# fpga_io.net
KiCad netlist of a schematic drawn in Altium Designer
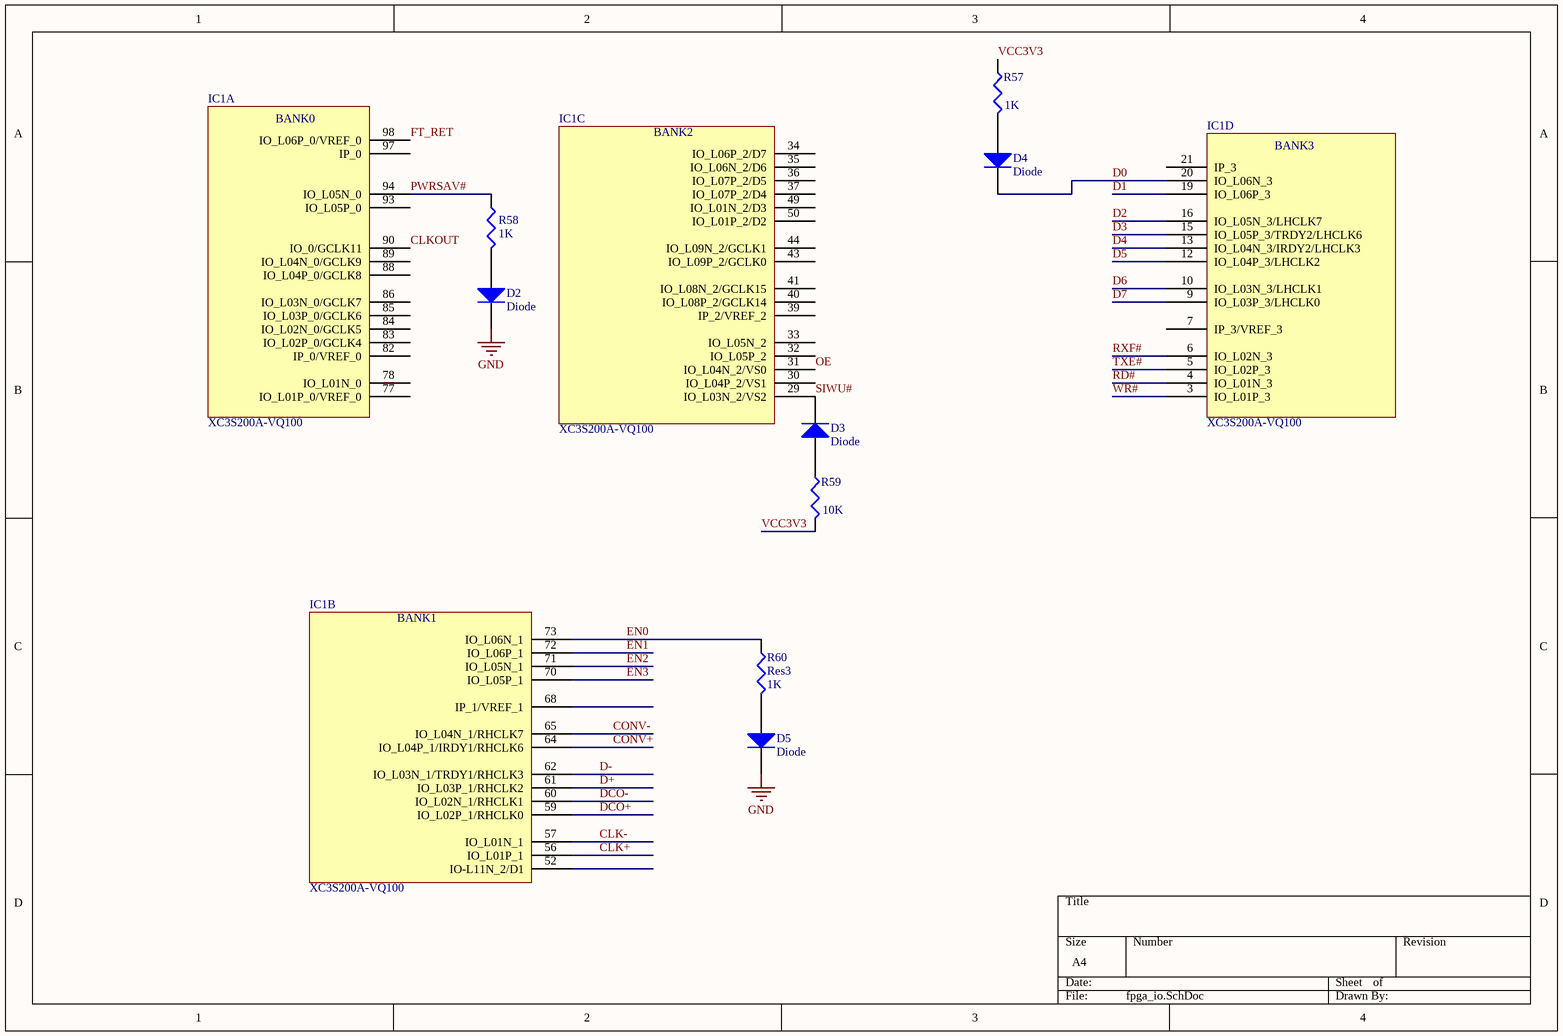
[diagram p0: fpga_io.SchDoc]

(export (version "E")
  (design (tool "Eeschema 10.0.6"))
  (components
    (comp (ref "D2")
      (value "Diode")
      (footprint "LED0603")
      (description "Default Diode")
      (fields (field (name "PUBLISHER") "Altium Limited"))
      (libsource (lib "Miscellaneous Devices") (part "Diode"))
    )
    (comp (ref "D3")
      (value "Diode")
      (footprint "LED0603")
      (description "Default Diode")
      (fields (field (name "PUBLISHER") "Altium Limited"))
      (libsource (lib "Miscellaneous Devices") (part "Diode"))
    )
    (comp (ref "D4")
      (value "Diode")
      (footprint "LED0603")
      (description "Default Diode")
      (fields (field (name "PUBLISHER") "Altium Limited"))
      (libsource (lib "Miscellaneous Devices") (part "Diode"))
    )
    (comp (ref "D5")
      (value "Diode")
      (footprint "LED0603")
      (description "Default Diode")
      (fields (field (name "PUBLISHER") "Altium Limited"))
      (libsource (lib "Miscellaneous Devices") (part "Diode"))
    )
    (comp (ref "IC1")
      (value "XC3S200A-VQ100")
      (footprint "QFP50P1600X1600X120-100N")
      (libsource (lib "nir_usb") (part "XC3S200A-VQ100"))
    )
    (comp (ref "R57")
      (value "1K")
      (footprint "J1-0603")
      (description "Resistor")
      (fields (field (name "Comment") "Res3") (field (name "PUBLISHER") "Altium Limited"))
      (libsource (lib "Miscellaneous Devices") (part "Res3"))
    )
    (comp (ref "R58")
      (value "1K")
      (footprint "J1-0603")
      (description "Resistor")
      (fields (field (name "Comment") "Res3") (field (name "PUBLISHER") "Altium Limited"))
      (libsource (lib "Miscellaneous Devices") (part "Res3"))
    )
    (comp (ref "R59")
      (value "10K")
      (footprint "J1-0603")
      (description "Resistor")
      (fields (field (name "Comment") "Res3") (field (name "PUBLISHER") "Altium Limited"))
      (libsource (lib "Miscellaneous Devices") (part "Res3"))
    )
    (comp (ref "R60")
      (value "Res3")
      (footprint "J1-0603")
      (description "Resistor")
      (fields (field (name "ALTIUM_VALUE") "1K") (field (name "PUBLISHER") "Altium Limited"))
      (libsource (lib "Miscellaneous Devices") (part "Res3"))
    )
  )
  (nets
    (net (code "1") (name "/CLK+") (class "Default")
      (node (ref "IC1") (pin "56") (pinfunction "IO_L01P_1_56") (pintype "passive"))
    )
    (net (code "2") (name "/CLK-") (class "Default")
      (node (ref "IC1") (pin "57") (pinfunction "IO_L01N_1_57") (pintype "passive"))
    )
    (net (code "3") (name "/CLKOUT") (class "Default")
      (node (ref "IC1") (pin "90") (pinfunction "IO_0/GCLK11_90") (pintype "passive"))
    )
    (net (code "4") (name "/CONV+") (class "Default")
      (node (ref "IC1") (pin "64") (pinfunction "IO_L04P_1/IRDY1/RHCLK6_64") (pintype "passive"))
    )
    (net (code "5") (name "/CONV-") (class "Default")
      (node (ref "IC1") (pin "65") (pinfunction "IO_L04N_1/RHCLK7_65") (pintype "passive"))
    )
    (net (code "6") (name "/D+") (class "Default")
      (node (ref "IC1") (pin "61") (pinfunction "IO_L03P_1/RHCLK2_61") (pintype "passive"))
    )
    (net (code "7") (name "/D-") (class "Default")
      (node (ref "IC1") (pin "62") (pinfunction "IO_L03N_1/TRDY1/RHCLK3_62") (pintype "passive"))
    )
    (net (code "8") (name "/D0") (class "Default")
      (node (ref "D4") (pin "2") (pinfunction "K_2") (pintype "passive"))
      (node (ref "IC1") (pin "20") (pinfunction "IO_L06N_3_20") (pintype "passive"))
    )
    (net (code "9") (name "/D1") (class "Default")
      (node (ref "IC1") (pin "19") (pinfunction "IO_L06P_3_19") (pintype "passive"))
    )
    (net (code "10") (name "/D2") (class "Default")
      (node (ref "IC1") (pin "16") (pinfunction "IO_L05N_3/LHCLK7_16") (pintype "passive"))
    )
    (net (code "11") (name "/D3") (class "Default")
      (node (ref "IC1") (pin "15") (pinfunction "IO_L05P_3/TRDY2/LHCLK6_15") (pintype "passive"))
    )
    (net (code "12") (name "/D4") (class "Default")
      (node (ref "IC1") (pin "13") (pinfunction "IO_L04N_3/IRDY2/LHCLK3_13") (pintype "passive"))
    )
    (net (code "13") (name "/D5") (class "Default")
      (node (ref "IC1") (pin "12") (pinfunction "IO_L04P_3/LHCLK2_12") (pintype "passive"))
    )
    (net (code "14") (name "/D6") (class "Default")
      (node (ref "IC1") (pin "10") (pinfunction "IO_L03N_3/LHCLK1_10") (pintype "passive"))
    )
    (net (code "15") (name "/D7") (class "Default")
      (node (ref "IC1") (pin "9") (pinfunction "IO_L03P_3/LHCLK0_9") (pintype "passive"))
    )
    (net (code "16") (name "/DCO+") (class "Default")
      (node (ref "IC1") (pin "59") (pinfunction "IO_L02P_1/RHCLK0_59") (pintype "passive"))
    )
    (net (code "17") (name "/DCO-") (class "Default")
      (node (ref "IC1") (pin "60") (pinfunction "IO_L02N_1/RHCLK1_60") (pintype "passive"))
    )
    (net (code "18") (name "/EN0") (class "Default")
      (node (ref "IC1") (pin "73") (pinfunction "IO_L06N_1_73") (pintype "passive"))
      (node (ref "R60") (pin "1") (pinfunction "1_1") (pintype "passive"))
    )
    (net (code "19") (name "/EN1") (class "Default")
      (node (ref "IC1") (pin "72") (pinfunction "IO_L06P_1_72") (pintype "passive"))
    )
    (net (code "20") (name "/EN2") (class "Default")
      (node (ref "IC1") (pin "71") (pinfunction "IO_L05N_1_71") (pintype "passive"))
    )
    (net (code "21") (name "/EN3") (class "Default")
      (node (ref "IC1") (pin "70") (pinfunction "IO_L05P_1_70") (pintype "passive"))
    )
    (net (code "22") (name "/FT_RET") (class "Default")
      (node (ref "IC1") (pin "98") (pinfunction "IO_L06P_0/VREF_0_98") (pintype "passive"))
    )
    (net (code "23") (name "/OE") (class "Default")
      (node (ref "IC1") (pin "31") (pinfunction "IO_L04N_2/VS0_31") (pintype "passive"))
    )
    (net (code "24") (name "/PWRSAV#") (class "Default")
      (node (ref "IC1") (pin "94") (pinfunction "IO_L05N_0_94") (pintype "passive"))
      (node (ref "R58") (pin "1") (pinfunction "1_1") (pintype "passive"))
    )
    (net (code "25") (name "/RD#") (class "Default")
      (node (ref "IC1") (pin "4") (pinfunction "IO_L01N_3_4") (pintype "passive"))
    )
    (net (code "26") (name "/RXF#") (class "Default")
      (node (ref "IC1") (pin "6") (pinfunction "IO_L02N_3_6") (pintype "passive"))
    )
    (net (code "27") (name "/SIWU#") (class "Default")
      (node (ref "D3") (pin "2") (pinfunction "K_2") (pintype "passive"))
      (node (ref "IC1") (pin "29") (pinfunction "IO_L03N_2/VS2_29") (pintype "passive"))
    )
    (net (code "28") (name "/TXE#") (class "Default")
      (node (ref "IC1") (pin "5") (pinfunction "IO_L02P_3_5") (pintype "passive"))
    )
    (net (code "29") (name "/VCC3V3") (class "Default")
      (node (ref "R57") (pin "1") (pinfunction "1_1") (pintype "passive"))
      (node (ref "R59") (pin "2") (pinfunction "2_2") (pintype "passive"))
    )
    (net (code "30") (name "/WR#") (class "Default")
      (node (ref "IC1") (pin "3") (pinfunction "IO_L01P_3_3") (pintype "passive"))
    )
    (net (code "31") (name "GND") (class "Default")
      (node (ref "D2") (pin "2") (pinfunction "K_2") (pintype "passive"))
      (node (ref "D5") (pin "2") (pinfunction "K_2") (pintype "passive"))
    )
    (net (code "32") (name "Net-(D2-A)") (class "Default")
      (node (ref "D2") (pin "1") (pinfunction "A_1") (pintype "passive"))
      (node (ref "R58") (pin "2") (pinfunction "2_2") (pintype "passive"))
    )
    (net (code "33") (name "Net-(D3-A)") (class "Default")
      (node (ref "D3") (pin "1") (pinfunction "A_1") (pintype "passive"))
      (node (ref "R59") (pin "1") (pinfunction "1_1") (pintype "passive"))
    )
    (net (code "34") (name "Net-(D4-A)") (class "Default")
      (node (ref "D4") (pin "1") (pinfunction "A_1") (pintype "passive"))
      (node (ref "R57") (pin "2") (pinfunction "2_2") (pintype "passive"))
    )
    (net (code "35") (name "Net-(D5-A)") (class "Default")
      (node (ref "D5") (pin "1") (pinfunction "A_1") (pintype "passive"))
      (node (ref "R60") (pin "2") (pinfunction "2_2") (pintype "passive"))
    )
    (net (code "36") (name "unconnected-(IC1A-IO_L01N_0-Pad78)") (class "Default")
      (node (ref "IC1") (pin "78") (pinfunction "IO_L01N_0_78") (pintype "passive"))
    )
    (net (code "37") (name "unconnected-(IC1A-IO_L01P_0{slash}VREF_0-Pad77)") (class "Default")
      (node (ref "IC1") (pin "77") (pinfunction "IO_L01P_0/VREF_0_77") (pintype "passive"))
    )
    (net (code "38") (name "unconnected-(IC1A-IO_L02N_0{slash}GCLK5-Pad84)") (class "Default")
      (node (ref "IC1") (pin "84") (pinfunction "IO_L02N_0/GCLK5_84") (pintype "passive"))
    )
    (net (code "39") (name "unconnected-(IC1A-IO_L02P_0{slash}GCLK4-Pad83)") (class "Default")
      (node (ref "IC1") (pin "83") (pinfunction "IO_L02P_0/GCLK4_83") (pintype "passive"))
    )
    (net (code "40") (name "unconnected-(IC1A-IO_L03N_0{slash}GCLK7-Pad86)") (class "Default")
      (node (ref "IC1") (pin "86") (pinfunction "IO_L03N_0/GCLK7_86") (pintype "passive"))
    )
    (net (code "41") (name "unconnected-(IC1A-IO_L03P_0{slash}GCLK6-Pad85)") (class "Default")
      (node (ref "IC1") (pin "85") (pinfunction "IO_L03P_0/GCLK6_85") (pintype "passive"))
    )
    (net (code "42") (name "unconnected-(IC1A-IO_L04N_0{slash}GCLK9-Pad89)") (class "Default")
      (node (ref "IC1") (pin "89") (pinfunction "IO_L04N_0/GCLK9_89") (pintype "passive"))
    )
    (net (code "43") (name "unconnected-(IC1A-IO_L04P_0{slash}GCLK8-Pad88)") (class "Default")
      (node (ref "IC1") (pin "88") (pinfunction "IO_L04P_0/GCLK8_88") (pintype "passive"))
    )
    (net (code "44") (name "unconnected-(IC1A-IO_L05P_0-Pad93)") (class "Default")
      (node (ref "IC1") (pin "93") (pinfunction "IO_L05P_0_93") (pintype "passive"))
    )
    (net (code "45") (name "unconnected-(IC1A-IP_0-Pad97)") (class "Default")
      (node (ref "IC1") (pin "97") (pinfunction "IP_0_97") (pintype "passive"))
    )
    (net (code "46") (name "unconnected-(IC1A-IP_0{slash}VREF_0-Pad82)") (class "Default")
      (node (ref "IC1") (pin "82") (pinfunction "IP_0/VREF_0_82") (pintype "passive"))
    )
    (net (code "47") (name "unconnected-(IC1B-IO-L11N_2{slash}D1-Pad52)") (class "Default")
      (node (ref "IC1") (pin "52") (pinfunction "IO-L11N_2/D1_52") (pintype "passive"))
    )
    (net (code "48") (name "unconnected-(IC1B-IP_1{slash}VREF_1-Pad68)") (class "Default")
      (node (ref "IC1") (pin "68") (pinfunction "IP_1/VREF_1_68") (pintype "passive"))
    )
    (net (code "49") (name "unconnected-(IC1C-IO_L01N_2{slash}D3-Pad49)") (class "Default")
      (node (ref "IC1") (pin "49") (pinfunction "IO_L01N_2/D3_49") (pintype "passive"))
    )
    (net (code "50") (name "unconnected-(IC1C-IO_L01P_2{slash}D2-Pad50)") (class "Default")
      (node (ref "IC1") (pin "50") (pinfunction "IO_L01P_2/D2_50") (pintype "passive"))
    )
    (net (code "51") (name "unconnected-(IC1C-IO_L04P_2{slash}VS1-Pad30)") (class "Default")
      (node (ref "IC1") (pin "30") (pinfunction "IO_L04P_2/VS1_30") (pintype "passive"))
    )
    (net (code "52") (name "unconnected-(IC1C-IO_L05N_2-Pad33)") (class "Default")
      (node (ref "IC1") (pin "33") (pinfunction "IO_L05N_2_33") (pintype "passive"))
    )
    (net (code "53") (name "unconnected-(IC1C-IO_L05P_2-Pad32)") (class "Default")
      (node (ref "IC1") (pin "32") (pinfunction "IO_L05P_2_32") (pintype "passive"))
    )
    (net (code "54") (name "unconnected-(IC1C-IO_L06N_2{slash}D6-Pad35)") (class "Default")
      (node (ref "IC1") (pin "35") (pinfunction "IO_L06N_2/D6_35") (pintype "passive"))
    )
    (net (code "55") (name "unconnected-(IC1C-IO_L06P_2{slash}D7-Pad34)") (class "Default")
      (node (ref "IC1") (pin "34") (pinfunction "IO_L06P_2/D7_34") (pintype "passive"))
    )
    (net (code "56") (name "unconnected-(IC1C-IO_L07P_2{slash}D4-Pad37)") (class "Default")
      (node (ref "IC1") (pin "37") (pinfunction "IO_L07P_2/D4_37") (pintype "passive"))
    )
    (net (code "57") (name "unconnected-(IC1C-IO_L07P_2{slash}D5-Pad36)") (class "Default")
      (node (ref "IC1") (pin "36") (pinfunction "IO_L07P_2/D5_36") (pintype "passive"))
    )
    (net (code "58") (name "unconnected-(IC1C-IO_L08N_2{slash}GCLK15-Pad41)") (class "Default")
      (node (ref "IC1") (pin "41") (pinfunction "IO_L08N_2/GCLK15_41") (pintype "passive"))
    )
    (net (code "59") (name "unconnected-(IC1C-IO_L08P_2{slash}GCLK14-Pad40)") (class "Default")
      (node (ref "IC1") (pin "40") (pinfunction "IO_L08P_2/GCLK14_40") (pintype "passive"))
    )
    (net (code "60") (name "unconnected-(IC1C-IO_L09N_2{slash}GCLK1-Pad44)") (class "Default")
      (node (ref "IC1") (pin "44") (pinfunction "IO_L09N_2/GCLK1_44") (pintype "passive"))
    )
    (net (code "61") (name "unconnected-(IC1C-IO_L09P_2{slash}GCLK0-Pad43)") (class "Default")
      (node (ref "IC1") (pin "43") (pinfunction "IO_L09P_2/GCLK0_43") (pintype "passive"))
    )
    (net (code "62") (name "unconnected-(IC1C-IP_2{slash}VREF_2-Pad39)") (class "Default")
      (node (ref "IC1") (pin "39") (pinfunction "IP_2/VREF_2_39") (pintype "passive"))
    )
    (net (code "63") (name "unconnected-(IC1D-IP_3-Pad21)") (class "Default")
      (node (ref "IC1") (pin "21") (pinfunction "IP_3_21") (pintype "passive"))
    )
    (net (code "64") (name "unconnected-(IC1D-IP_3{slash}VREF_3-Pad7)") (class "Default")
      (node (ref "IC1") (pin "7") (pinfunction "IP_3/VREF_3_7") (pintype "passive"))
    )
  )
)
